# load-cell.net
KiCad netlist of a schematic drawn in Altium Designer
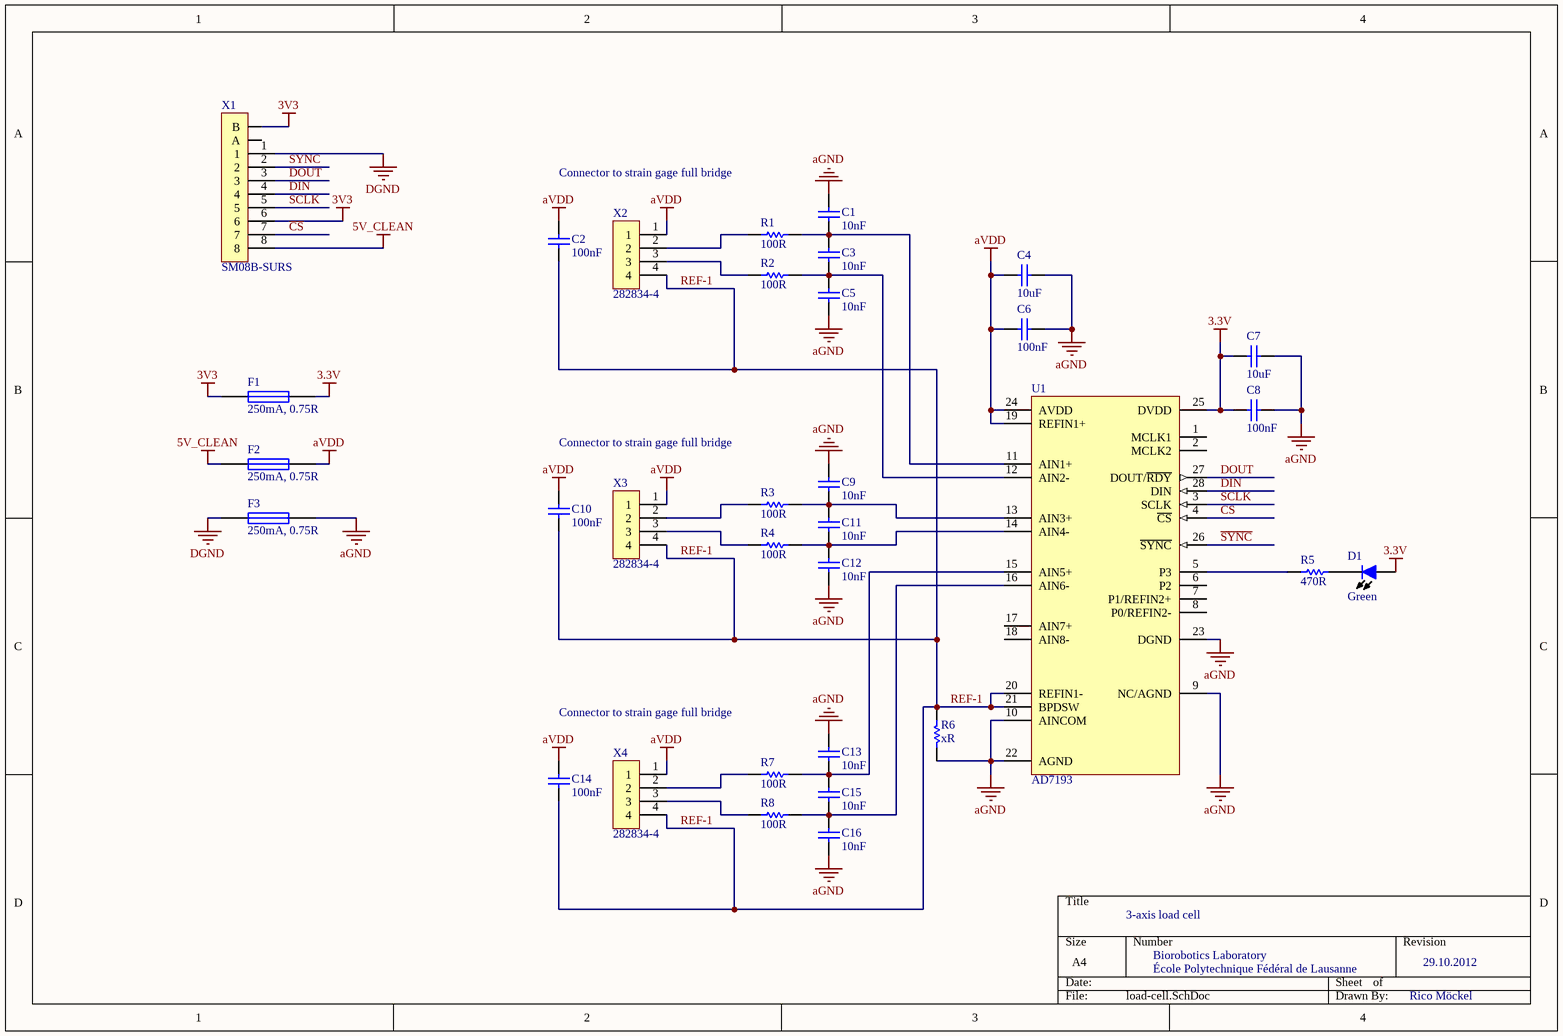
[diagram p0: load-cell.SchDoc]

(export (version "E")
  (design (tool "Eeschema 10.0.6"))
  (components
    (comp (ref "C1")
      (value "10nF")
      (footprint "CAPC1608L")
      (description "Capacitor")
      (fields (field (name "PUBLISHER") "Altium Limited"))
      (libsource (lib "Miscellaneous Devices") (part "Cap"))
    )
    (comp (ref "C2")
      (value "100nF")
      (footprint "CAPC1608L")
      (description "Capacitor")
      (fields (field (name "PUBLISHER") "Altium Limited"))
      (libsource (lib "Miscellaneous Devices") (part "Cap"))
    )
    (comp (ref "C3")
      (value "10nF")
      (footprint "CAPC1608L")
      (description "Capacitor")
      (fields (field (name "PUBLISHER") "Altium Limited"))
      (libsource (lib "Miscellaneous Devices") (part "Cap"))
    )
    (comp (ref "C4")
      (value "10uF")
      (footprint "CAPC1608L")
      (description "Capacitor")
      (fields (field (name "PUBLISHER") "Altium Limited"))
      (libsource (lib "Miscellaneous Devices") (part "Cap"))
    )
    (comp (ref "C5")
      (value "10nF")
      (footprint "CAPC1608L")
      (description "Capacitor")
      (fields (field (name "PUBLISHER") "Altium Limited"))
      (libsource (lib "Miscellaneous Devices") (part "Cap"))
    )
    (comp (ref "C6")
      (value "100nF")
      (footprint "CAPC1608L")
      (description "Capacitor")
      (fields (field (name "PUBLISHER") "Altium Limited"))
      (libsource (lib "Miscellaneous Devices") (part "Cap"))
    )
    (comp (ref "C7")
      (value "10uF")
      (footprint "CAPC1608L")
      (description "Capacitor")
      (fields (field (name "PUBLISHER") "Altium Limited"))
      (libsource (lib "Miscellaneous Devices") (part "Cap"))
    )
    (comp (ref "C8")
      (value "100nF")
      (footprint "CAPC1608L")
      (description "Capacitor")
      (fields (field (name "PUBLISHER") "Altium Limited"))
      (libsource (lib "Miscellaneous Devices") (part "Cap"))
    )
    (comp (ref "C9")
      (value "10nF")
      (footprint "CAPC1608L")
      (description "Capacitor")
      (fields (field (name "PUBLISHER") "Altium Limited"))
      (libsource (lib "Miscellaneous Devices") (part "Cap"))
    )
    (comp (ref "C10")
      (value "100nF")
      (footprint "CAPC1608L")
      (description "Capacitor")
      (fields (field (name "PUBLISHER") "Altium Limited"))
      (libsource (lib "Miscellaneous Devices") (part "Cap"))
    )
    (comp (ref "C11")
      (value "10nF")
      (footprint "CAPC1608L")
      (description "Capacitor")
      (fields (field (name "PUBLISHER") "Altium Limited"))
      (libsource (lib "Miscellaneous Devices") (part "Cap"))
    )
    (comp (ref "C12")
      (value "10nF")
      (footprint "CAPC1608L")
      (description "Capacitor")
      (fields (field (name "PUBLISHER") "Altium Limited"))
      (libsource (lib "Miscellaneous Devices") (part "Cap"))
    )
    (comp (ref "C13")
      (value "10nF")
      (footprint "CAPC1608L")
      (description "Capacitor")
      (fields (field (name "PUBLISHER") "Altium Limited"))
      (libsource (lib "Miscellaneous Devices") (part "Cap"))
    )
    (comp (ref "C14")
      (value "100nF")
      (footprint "CAPC1608L")
      (description "Capacitor")
      (fields (field (name "PUBLISHER") "Altium Limited"))
      (libsource (lib "Miscellaneous Devices") (part "Cap"))
    )
    (comp (ref "C15")
      (value "10nF")
      (footprint "CAPC1608L")
      (description "Capacitor")
      (fields (field (name "PUBLISHER") "Altium Limited"))
      (libsource (lib "Miscellaneous Devices") (part "Cap"))
    )
    (comp (ref "C16")
      (value "10nF")
      (footprint "CAPC1608L")
      (description "Capacitor")
      (fields (field (name "PUBLISHER") "Altium Limited"))
      (libsource (lib "Miscellaneous Devices") (part "Cap"))
    )
    (comp (ref "D1")
      (value "LED Green")
      (footprint "RESC1005N")
      (description "LED")
      (fields (field (name "COLOR") "Green"))
      (libsource (lib "Roombots") (part "LED"))
    )
    (comp (ref "F1")
      (value "250mA, 0.75R")
      (footprint "RESC1608L")
      (description "Ferrit Bead")
      (fields (field (name "PUBLISHER") "Altium Limited"))
      (libsource (lib "Miscellaneous Devices") (part "Fuse 1"))
    )
    (comp (ref "F2")
      (value "250mA, 0.75R")
      (footprint "RESC1608L")
      (description "Ferrit Bead")
      (fields (field (name "PUBLISHER") "Altium Limited"))
      (libsource (lib "Miscellaneous Devices") (part "Fuse 1"))
    )
    (comp (ref "F3")
      (value "250mA, 0.75R")
      (footprint "RESC1608L")
      (description "Ferrit Bead")
      (fields (field (name "PUBLISHER") "Altium Limited"))
      (libsource (lib "Miscellaneous Devices") (part "Fuse 1"))
    )
    (comp (ref "R1")
      (value "100R")
      (footprint "RESC1608L")
      (description "Resistor")
      (fields (field (name "PUBLISHER") "Altium Limited"))
      (libsource (lib "Miscellaneous Devices") (part "Res1"))
    )
    (comp (ref "R2")
      (value "100R")
      (footprint "RESC1608L")
      (description "Resistor")
      (fields (field (name "PUBLISHER") "Altium Limited"))
      (libsource (lib "Miscellaneous Devices") (part "Res1"))
    )
    (comp (ref "R3")
      (value "100R")
      (footprint "RESC1608L")
      (description "Resistor")
      (fields (field (name "PUBLISHER") "Altium Limited"))
      (libsource (lib "Miscellaneous Devices") (part "Res1"))
    )
    (comp (ref "R4")
      (value "100R")
      (footprint "RESC1608L")
      (description "Resistor")
      (fields (field (name "PUBLISHER") "Altium Limited"))
      (libsource (lib "Miscellaneous Devices") (part "Res1"))
    )
    (comp (ref "R5")
      (value "470R")
      (footprint "RESC1608L")
      (description "Resistor")
      (fields (field (name "PUBLISHER") "Altium Limited"))
      (libsource (lib "Miscellaneous Devices") (part "Res1"))
    )
    (comp (ref "R6")
      (value "xR")
      (footprint "RESC1608L")
      (description "Resistor")
      (fields (field (name "PUBLISHER") "Altium Limited"))
      (libsource (lib "Miscellaneous Devices") (part "Res1"))
    )
    (comp (ref "R7")
      (value "100R")
      (footprint "RESC1608L")
      (description "Resistor")
      (fields (field (name "PUBLISHER") "Altium Limited"))
      (libsource (lib "Miscellaneous Devices") (part "Res1"))
    )
    (comp (ref "R8")
      (value "100R")
      (footprint "RESC1608L")
      (description "Resistor")
      (fields (field (name "PUBLISHER") "Altium Limited"))
      (libsource (lib "Miscellaneous Devices") (part "Res1"))
    )
    (comp (ref "U1")
      (value "AD7193")
      (footprint "TSSOP65-28N-NO_TP")
      (description "4-channel 24-bit ADC with PGA")
      (libsource (lib "Roombots") (part "AD7193_TSSOP"))
    )
    (comp (ref "X1")
      (value "SM08B-SURS")
      (footprint "SM08B-SURS")
      (description "wire-to-board connector")
      (libsource (lib "Roombots") (part "SM08B-SURS"))
    )
    (comp (ref "X2")
      (value "282834-4")
      (footprint "282834-4")
      (description "4-pin connector with screw contacts")
      (fields (field (name "MANUFACTURER") "TE CONNECTIVITY / BUCHANAN"))
      (libsource (lib "Connectors") (part "4x1 282834-4"))
    )
    (comp (ref "X3")
      (value "282834-4")
      (footprint "282834-4")
      (description "4-pin connector with screw contacts")
      (fields (field (name "MANUFACTURER") "TE CONNECTIVITY / BUCHANAN"))
      (libsource (lib "Connectors") (part "4x1 282834-4"))
    )
    (comp (ref "X4")
      (value "282834-4")
      (footprint "282834-4")
      (description "4-pin connector with screw contacts")
      (fields (field (name "MANUFACTURER") "TE CONNECTIVITY / BUCHANAN"))
      (libsource (lib "Connectors") (part "4x1 282834-4"))
    )
  )
  (nets
    (net (code "1") (name "/DIN") (class "Default")
      (node (ref "U1") (pin "28") (pinfunction "DIN_28") (pintype "input"))
      (node (ref "X1") (pin "4") (pinfunction "4_4") (pintype "passive"))
    )
    (net (code "2") (name "/DOUT") (class "Default")
      (node (ref "U1") (pin "27") (pinfunction "DOUT/~{RDY}_27") (pintype "output"))
      (node (ref "X1") (pin "3") (pinfunction "3_3") (pintype "passive"))
    )
    (net (code "3") (name "/REF-1") (class "Default")
      (node (ref "C10") (pin "1") (pinfunction "1_1") (pintype "passive"))
      (node (ref "C14") (pin "1") (pinfunction "1_1") (pintype "passive"))
      (node (ref "C2") (pin "1") (pinfunction "1_1") (pintype "passive"))
      (node (ref "R6") (pin "1") (pinfunction "1_1") (pintype "passive"))
      (node (ref "U1") (pin "20") (pinfunction "REFIN1-_20") (pintype "passive"))
      (node (ref "U1") (pin "21") (pinfunction "BPDSW_21") (pintype "passive"))
      (node (ref "X2") (pin "4") (pinfunction "4_4") (pintype "passive"))
      (node (ref "X3") (pin "4") (pinfunction "4_4") (pintype "passive"))
      (node (ref "X4") (pin "4") (pinfunction "4_4") (pintype "passive"))
    )
    (net (code "4") (name "/SCLK") (class "Default")
      (node (ref "U1") (pin "3") (pinfunction "SCLK_3") (pintype "input"))
      (node (ref "X1") (pin "5") (pinfunction "5_5") (pintype "passive"))
    )
    (net (code "5") (name "/~{CS}") (class "Default")
      (node (ref "U1") (pin "4") (pinfunction "~{CS}_4") (pintype "input"))
      (node (ref "X1") (pin "7") (pinfunction "7_7") (pintype "passive"))
    )
    (net (code "6") (name "/~{SYNC}") (class "Default")
      (node (ref "U1") (pin "26") (pinfunction "~{SYNC}_26") (pintype "input"))
      (node (ref "X1") (pin "2") (pinfunction "2_2") (pintype "passive"))
    )
    (net (code "7") (name "3.3V") (class "Default")
      (node (ref "C7") (pin "2") (pinfunction "2_2") (pintype "passive"))
      (node (ref "C8") (pin "2") (pinfunction "2_2") (pintype "passive"))
      (node (ref "D1") (pin "1") (pinfunction "A_1") (pintype "passive"))
      (node (ref "F1") (pin "2") (pinfunction "2_2") (pintype "passive"))
      (node (ref "U1") (pin "25") (pinfunction "DVDD_25") (pintype "passive"))
    )
    (net (code "8") (name "3V3") (class "Default")
      (node (ref "F1") (pin "1") (pinfunction "1_1") (pintype "passive"))
      (node (ref "X1") (pin "6") (pinfunction "6_6") (pintype "passive"))
      (node (ref "X1") (pin "B") (pinfunction "B_B") (pintype "passive"))
    )
    (net (code "9") (name "5V_CLEAN") (class "Default")
      (node (ref "F2") (pin "1") (pinfunction "1_1") (pintype "passive"))
      (node (ref "X1") (pin "8") (pinfunction "8_8") (pintype "passive"))
    )
    (net (code "10") (name "DGND") (class "Default")
      (node (ref "F3") (pin "1") (pinfunction "1_1") (pintype "passive"))
      (node (ref "X1") (pin "1") (pinfunction "1_1") (pintype "passive"))
    )
    (net (code "11") (name "Net-(D1-C)") (class "Default")
      (node (ref "D1") (pin "2") (pinfunction "C_2") (pintype "passive"))
      (node (ref "R5") (pin "2") (pinfunction "2_2") (pintype "passive"))
    )
    (net (code "12") (name "Net-(R1-Pad1)") (class "Default")
      (node (ref "R1") (pin "1") (pinfunction "1_1") (pintype "passive"))
      (node (ref "X2") (pin "2") (pinfunction "2_2") (pintype "passive"))
    )
    (net (code "13") (name "Net-(R2-Pad1)") (class "Default")
      (node (ref "R2") (pin "1") (pinfunction "1_1") (pintype "passive"))
      (node (ref "X2") (pin "3") (pinfunction "3_3") (pintype "passive"))
    )
    (net (code "14") (name "Net-(R3-Pad1)") (class "Default")
      (node (ref "R3") (pin "1") (pinfunction "1_1") (pintype "passive"))
      (node (ref "X3") (pin "2") (pinfunction "2_2") (pintype "passive"))
    )
    (net (code "15") (name "Net-(R4-Pad1)") (class "Default")
      (node (ref "R4") (pin "1") (pinfunction "1_1") (pintype "passive"))
      (node (ref "X3") (pin "3") (pinfunction "3_3") (pintype "passive"))
    )
    (net (code "16") (name "Net-(R7-Pad1)") (class "Default")
      (node (ref "R7") (pin "1") (pinfunction "1_1") (pintype "passive"))
      (node (ref "X4") (pin "2") (pinfunction "2_2") (pintype "passive"))
    )
    (net (code "17") (name "Net-(R8-Pad1)") (class "Default")
      (node (ref "R8") (pin "1") (pinfunction "1_1") (pintype "passive"))
      (node (ref "X4") (pin "3") (pinfunction "3_3") (pintype "passive"))
    )
    (net (code "18") (name "Net-(U1-AIN1+)") (class "Default")
      (node (ref "C1") (pin "2") (pinfunction "2_2") (pintype "passive"))
      (node (ref "C3") (pin "1") (pinfunction "1_1") (pintype "passive"))
      (node (ref "R1") (pin "2") (pinfunction "2_2") (pintype "passive"))
      (node (ref "U1") (pin "11") (pinfunction "AIN1+_11") (pintype "passive"))
    )
    (net (code "19") (name "Net-(U1-AIN2-)") (class "Default")
      (node (ref "C3") (pin "2") (pinfunction "2_2") (pintype "passive"))
      (node (ref "C5") (pin "1") (pinfunction "1_1") (pintype "passive"))
      (node (ref "R2") (pin "2") (pinfunction "2_2") (pintype "passive"))
      (node (ref "U1") (pin "12") (pinfunction "AIN2-_12") (pintype "passive"))
    )
    (net (code "20") (name "Net-(U1-AIN3+)") (class "Default")
      (node (ref "C11") (pin "1") (pinfunction "1_1") (pintype "passive"))
      (node (ref "C9") (pin "2") (pinfunction "2_2") (pintype "passive"))
      (node (ref "R3") (pin "2") (pinfunction "2_2") (pintype "passive"))
      (node (ref "U1") (pin "13") (pinfunction "AIN3+_13") (pintype "passive"))
    )
    (net (code "21") (name "Net-(U1-AIN4-)") (class "Default")
      (node (ref "C11") (pin "2") (pinfunction "2_2") (pintype "passive"))
      (node (ref "C12") (pin "1") (pinfunction "1_1") (pintype "passive"))
      (node (ref "R4") (pin "2") (pinfunction "2_2") (pintype "passive"))
      (node (ref "U1") (pin "14") (pinfunction "AIN4-_14") (pintype "passive"))
    )
    (net (code "22") (name "Net-(U1-AIN5+)") (class "Default")
      (node (ref "C13") (pin "2") (pinfunction "2_2") (pintype "passive"))
      (node (ref "C15") (pin "1") (pinfunction "1_1") (pintype "passive"))
      (node (ref "R7") (pin "2") (pinfunction "2_2") (pintype "passive"))
      (node (ref "U1") (pin "15") (pinfunction "AIN5+_15") (pintype "passive"))
    )
    (net (code "23") (name "Net-(U1-AIN6-)") (class "Default")
      (node (ref "C15") (pin "2") (pinfunction "2_2") (pintype "passive"))
      (node (ref "C16") (pin "1") (pinfunction "1_1") (pintype "passive"))
      (node (ref "R8") (pin "2") (pinfunction "2_2") (pintype "passive"))
      (node (ref "U1") (pin "16") (pinfunction "AIN6-_16") (pintype "passive"))
    )
    (net (code "24") (name "Net-(U1-P3)") (class "Default")
      (node (ref "R5") (pin "1") (pinfunction "1_1") (pintype "passive"))
      (node (ref "U1") (pin "5") (pinfunction "P3_5") (pintype "passive"))
    )
    (net (code "25") (name "aGND") (class "Default")
      (node (ref "C1") (pin "1") (pinfunction "1_1") (pintype "passive"))
      (node (ref "C12") (pin "2") (pinfunction "2_2") (pintype "passive"))
      (node (ref "C13") (pin "1") (pinfunction "1_1") (pintype "passive"))
      (node (ref "C16") (pin "2") (pinfunction "2_2") (pintype "passive"))
      (node (ref "C4") (pin "1") (pinfunction "1_1") (pintype "passive"))
      (node (ref "C5") (pin "2") (pinfunction "2_2") (pintype "passive"))
      (node (ref "C6") (pin "1") (pinfunction "1_1") (pintype "passive"))
      (node (ref "C7") (pin "1") (pinfunction "1_1") (pintype "passive"))
      (node (ref "C8") (pin "1") (pinfunction "1_1") (pintype "passive"))
      (node (ref "C9") (pin "1") (pinfunction "1_1") (pintype "passive"))
      (node (ref "F3") (pin "2") (pinfunction "2_2") (pintype "passive"))
      (node (ref "R6") (pin "2") (pinfunction "2_2") (pintype "passive"))
      (node (ref "U1") (pin "10") (pinfunction "AINCOM_10") (pintype "passive"))
      (node (ref "U1") (pin "22") (pinfunction "AGND_22") (pintype "passive"))
      (node (ref "U1") (pin "23") (pinfunction "DGND_23") (pintype "passive"))
      (node (ref "U1") (pin "9") (pinfunction "NC/AGND_9") (pintype "passive"))
    )
    (net (code "26") (name "aVDD") (class "Default")
      (node (ref "C10") (pin "2") (pinfunction "2_2") (pintype "passive"))
      (node (ref "C14") (pin "2") (pinfunction "2_2") (pintype "passive"))
      (node (ref "C2") (pin "2") (pinfunction "2_2") (pintype "passive"))
      (node (ref "C4") (pin "2") (pinfunction "2_2") (pintype "passive"))
      (node (ref "C6") (pin "2") (pinfunction "2_2") (pintype "passive"))
      (node (ref "F2") (pin "2") (pinfunction "2_2") (pintype "passive"))
      (node (ref "U1") (pin "19") (pinfunction "REFIN1+_19") (pintype "passive"))
      (node (ref "U1") (pin "24") (pinfunction "AVDD_24") (pintype "passive"))
      (node (ref "X2") (pin "1") (pinfunction "1_1") (pintype "passive"))
      (node (ref "X3") (pin "1") (pinfunction "1_1") (pintype "passive"))
      (node (ref "X4") (pin "1") (pinfunction "1_1") (pintype "passive"))
    )
    (net (code "27") (name "unconnected-(U1-AIN7+-Pad17)") (class "Default")
      (node (ref "U1") (pin "17") (pinfunction "AIN7+_17") (pintype "passive"))
    )
    (net (code "28") (name "unconnected-(U1-AIN8--Pad18)") (class "Default")
      (node (ref "U1") (pin "18") (pinfunction "AIN8-_18") (pintype "passive"))
    )
    (net (code "29") (name "unconnected-(U1-MCLK1-Pad1)") (class "Default")
      (node (ref "U1") (pin "1") (pinfunction "MCLK1_1") (pintype "passive"))
    )
    (net (code "30") (name "unconnected-(U1-MCLK2-Pad2)") (class "Default")
      (node (ref "U1") (pin "2") (pinfunction "MCLK2_2") (pintype "passive"))
    )
    (net (code "31") (name "unconnected-(U1-P0{slash}REFIN2--Pad8)") (class "Default")
      (node (ref "U1") (pin "8") (pinfunction "P0/REFIN2-_8") (pintype "passive"))
    )
    (net (code "32") (name "unconnected-(U1-P1{slash}REFIN2+-Pad7)") (class "Default")
      (node (ref "U1") (pin "7") (pinfunction "P1/REFIN2+_7") (pintype "passive"))
    )
    (net (code "33") (name "unconnected-(U1-P2-Pad6)") (class "Default")
      (node (ref "U1") (pin "6") (pinfunction "P2_6") (pintype "passive"))
    )
    (net (code "34") (name "unconnected-(X1-PadA)") (class "Default")
      (node (ref "X1") (pin "A") (pinfunction "A_A") (pintype "passive"))
    )
  )
)
